# v1_0.net
KiCad netlist of a schematic drawn in Altium Designer
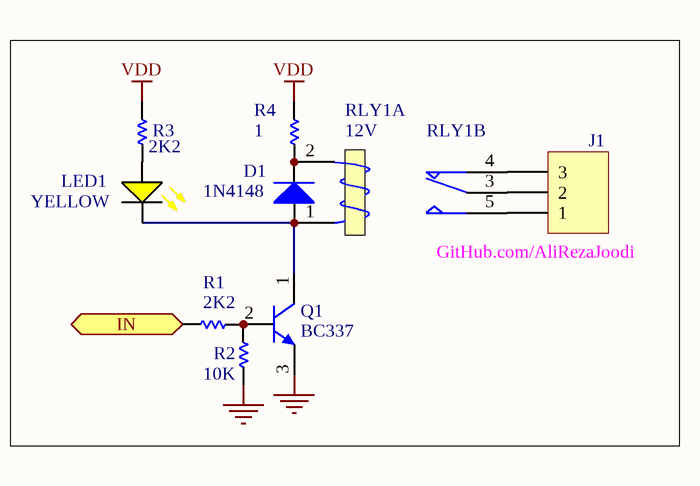
[diagram p0: v1.0.SchDoc]

(export (version "E")
  (design (tool "Eeschema 10.0.6"))
  (components
    (comp (ref "D1")
      (value "1N4148")
      (footprint "DIODE0.4_Glass")
      (description "Default Diode")
      (fields (field (name "MANUFACTURER") "Generic Components") (field (name "PUBLISHER") "Altium Limited"))
      (libsource (lib "Miscellaneous Devices") (part "Diode"))
    )
    (comp (ref "J1")
      (value "3PIN")
      (footprint "Fonics_3PIN_1")
      (description "Header, 3-Pin")
      (fields (field (name "MANUFACTURER") "Generic Components") (field (name "PUBLISHER") "Altium Limited"))
      (libsource (lib "Miscellaneous Connectors") (part "Header 3"))
    )
    (comp (ref "LED1")
      (value "YELLOW")
      (footprint "LED_THD_3MM_YELLOW_R")
      (description "LED, Yellow")
      (fields (field (name "MANUFACTURER") "Generic Components") (field (name "PUBLISHER") "Altium Limited"))
      (libsource (lib "Display") (part "LED_YELLOW"))
    )
    (comp (ref "Q1")
      (value "BC337")
      (footprint "TO92C")
      (description "NPN Bipolar Transistor")
      (fields (field (name "MANUFACTURER") "Generic Components") (field (name "PUBLISHER") "Altium Limited"))
      (libsource (lib "Miscellaneous Devices") (part "NPN"))
    )
    (comp (ref "R1")
      (value "2K2")
      (footprint "R_THD_AXIAL0.4(1/4W)")
      (description "Resistor")
      (libsource (lib "Passive") (part "Resistor"))
    )
    (comp (ref "R2")
      (value "10K")
      (footprint "R_THD_AXIAL0.4(1/4W)")
      (description "Resistor")
      (libsource (lib "Passive") (part "Resistor"))
    )
    (comp (ref "R3")
      (value "2K2")
      (footprint "R_THD_AXIAL0.4(1/4W)")
      (description "Resistor")
      (libsource (lib "Passive") (part "Resistor"))
    )
    (comp (ref "R4")
      (value "1")
      (footprint "R_THD_AXIAL0.4(1/4W)")
      (description "Resistor")
      (libsource (lib "Passive") (part "Resistor"))
    )
    (comp (ref "RLY1")
      (value "12V")
      (footprint "RELAY_SPDT_5PIN_2216")
      (description "SPDT Relay")
      (libsource (lib "Passive") (part "Relay_SPDT_2Form"))
    )
  )
  (nets
    (net (code "1") (name "/IN") (class "Default")
      (node (ref "R1") (pin "2") (pinfunction "2_2") (pintype "passive"))
    )
    (net (code "2") (name "GND") (class "Default")
      (node (ref "Q1") (pin "3") (pinfunction "E_3") (pintype "passive"))
      (node (ref "R2") (pin "1") (pinfunction "1_1") (pintype "passive"))
    )
    (net (code "3") (name "Net-(D1-A)") (class "Default")
      (node (ref "D1") (pin "1") (pinfunction "A_1") (pintype "passive"))
      (node (ref "LED1") (pin "2") (pinfunction "K_2") (pintype "passive"))
      (node (ref "Q1") (pin "1") (pinfunction "C_1") (pintype "passive"))
      (node (ref "RLY1") (pin "1") (pinfunction "T2_1") (pintype "passive"))
    )
    (net (code "4") (name "Net-(D1-K)") (class "Default")
      (node (ref "D1") (pin "2") (pinfunction "K_2") (pintype "passive"))
      (node (ref "R4") (pin "1") (pinfunction "1_1") (pintype "passive"))
      (node (ref "RLY1") (pin "2") (pinfunction "T1_2") (pintype "passive"))
    )
    (net (code "5") (name "Net-(LED1-A)") (class "Default")
      (node (ref "LED1") (pin "1") (pinfunction "A_1") (pintype "passive"))
      (node (ref "R3") (pin "1") (pinfunction "1_1") (pintype "passive"))
    )
    (net (code "6") (name "Net-(Q1-B)") (class "Default")
      (node (ref "Q1") (pin "2") (pinfunction "B_2") (pintype "passive"))
      (node (ref "R1") (pin "1") (pinfunction "1_1") (pintype "passive"))
      (node (ref "R2") (pin "2") (pinfunction "2_2") (pintype "passive"))
    )
    (net (code "7") (name "Net-(RLY1B-COM)") (class "Default")
      (node (ref "J1") (pin "2") (pinfunction "2_2") (pintype "passive"))
      (node (ref "RLY1") (pin "3") (pinfunction "COM_3") (pintype "passive"))
    )
    (net (code "8") (name "Net-(RLY1B-NC)") (class "Default")
      (node (ref "J1") (pin "3") (pinfunction "3_3") (pintype "passive"))
      (node (ref "RLY1") (pin "4") (pinfunction "NC_4") (pintype "passive"))
    )
    (net (code "9") (name "Net-(RLY1B-NO)") (class "Default")
      (node (ref "J1") (pin "1") (pinfunction "1_1") (pintype "passive"))
      (node (ref "RLY1") (pin "5") (pinfunction "NO_5") (pintype "passive"))
    )
    (net (code "10") (name "VDD") (class "Default")
      (node (ref "R3") (pin "2") (pinfunction "2_2") (pintype "passive"))
      (node (ref "R4") (pin "2") (pinfunction "2_2") (pintype "passive"))
    )
  )
)
